# design.net
KiCad netlist of a schematic drawn in Altium Designer
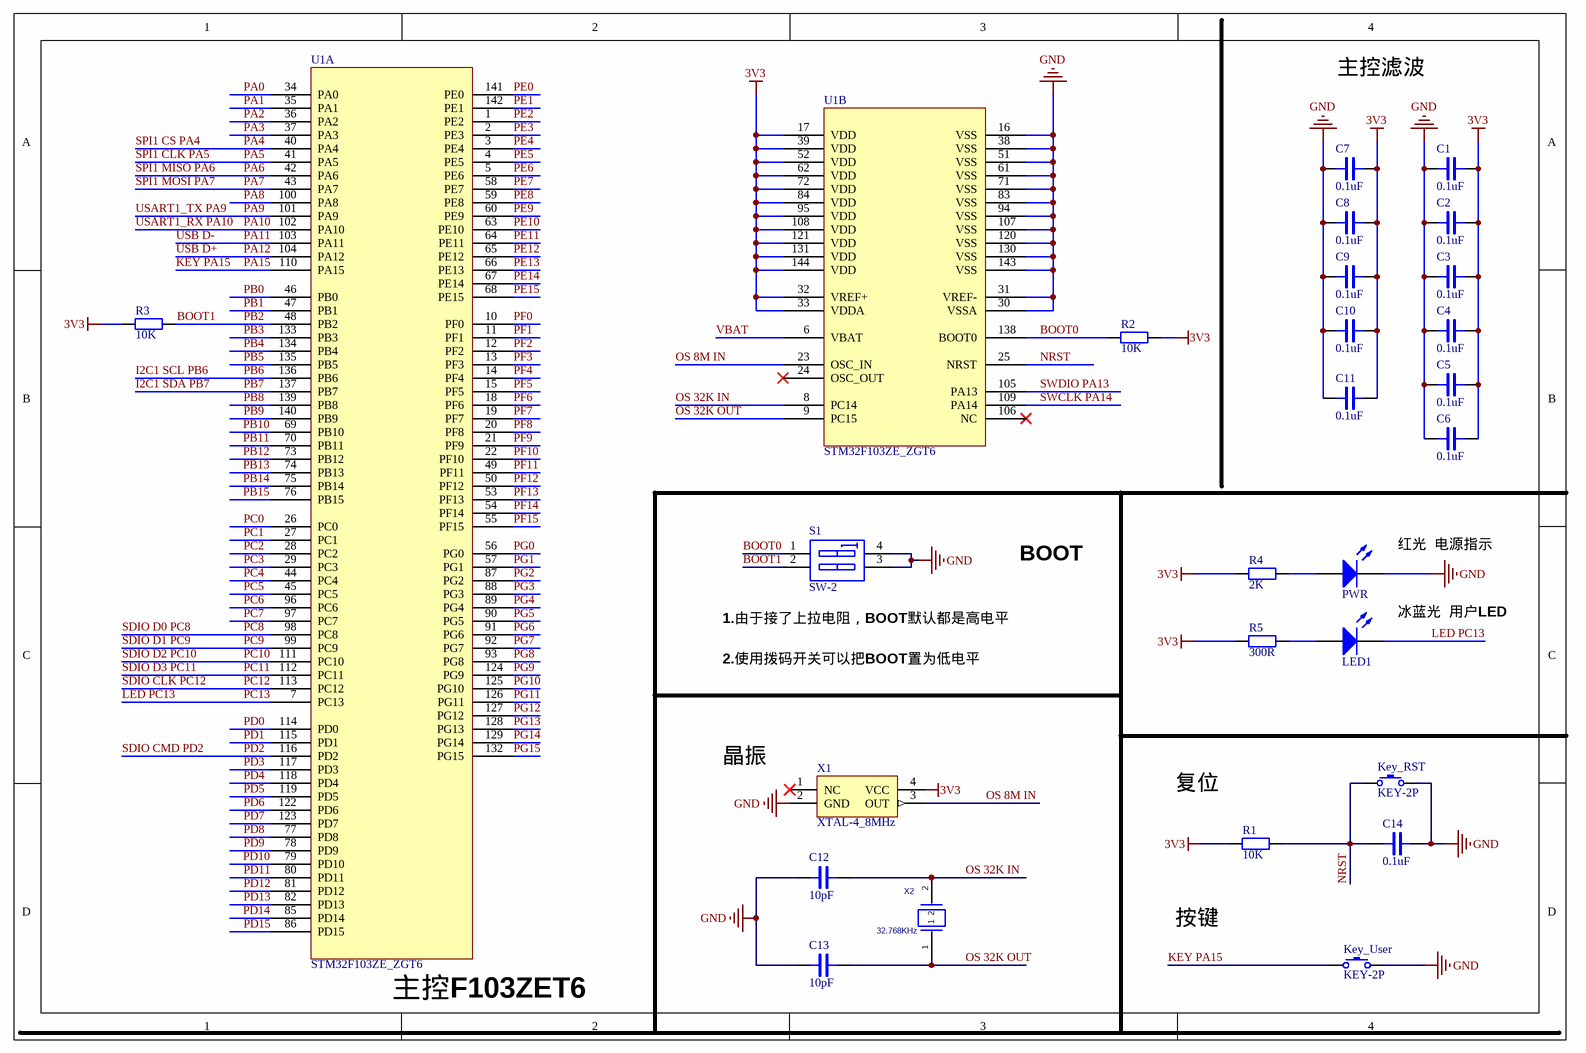
[diagram p0: 主控系统板.SchDoc]

(export (version "E")
  (design (tool "Eeschema 10.0.6"))
  (components
    (comp (ref "C1")
      (value "0.1uF")
      (footprint "0603")
      (description "Capacitor")
      (libsource (lib "General") (part "CAP"))
    )
    (comp (ref "C2")
      (value "0.1uF")
      (footprint "0603")
      (description "Capacitor")
      (libsource (lib "General") (part "CAP"))
    )
    (comp (ref "C3")
      (value "0.1uF")
      (footprint "0603")
      (description "Capacitor")
      (libsource (lib "General") (part "CAP"))
    )
    (comp (ref "C4")
      (value "0.1uF")
      (footprint "0603")
      (description "Capacitor")
      (libsource (lib "General") (part "CAP"))
    )
    (comp (ref "C5")
      (value "0.1uF")
      (footprint "0603")
      (description "Capacitor")
      (libsource (lib "General") (part "CAP"))
    )
    (comp (ref "C6")
      (value "0.1uF")
      (footprint "0603")
      (description "Capacitor")
      (libsource (lib "General") (part "CAP"))
    )
    (comp (ref "C7")
      (value "0.1uF")
      (footprint "0603")
      (description "Capacitor")
      (libsource (lib "General") (part "CAP"))
    )
    (comp (ref "C8")
      (value "0.1uF")
      (footprint "0603")
      (description "Capacitor")
      (libsource (lib "General") (part "CAP"))
    )
    (comp (ref "C9")
      (value "0.1uF")
      (footprint "0603")
      (description "Capacitor")
      (libsource (lib "General") (part "CAP"))
    )
    (comp (ref "C10")
      (value "0.1uF")
      (footprint "0603")
      (description "Capacitor")
      (libsource (lib "General") (part "CAP"))
    )
    (comp (ref "C11")
      (value "0.1uF")
      (footprint "0603")
      (description "Capacitor")
      (libsource (lib "General") (part "CAP"))
    )
    (comp (ref "C12")
      (value "10pF")
      (footprint "0603")
      (description "Capacitor")
      (libsource (lib "General") (part "CAP"))
    )
    (comp (ref "C13")
      (value "10pF")
      (footprint "0603")
      (description "Capacitor")
      (libsource (lib "General") (part "CAP"))
    )
    (comp (ref "C14")
      (value "0.1uF")
      (footprint "0603")
      (description "Capacitor")
      (libsource (lib "General") (part "CAP"))
    )
    (comp (ref "Key_RST")
      (value "KEY-2P")
      (footprint "TSW SMD-3*6*2.5")
      (description "Key")
      (libsource (lib "General") (part "KEY-2P"))
    )
    (comp (ref "Key_User")
      (value "KEY-2P")
      (footprint "TSW SMD-3*6*2.5")
      (description "Key")
      (libsource (lib "General") (part "KEY-2P"))
    )
    (comp (ref "LED1")
      (value "LED")
      (footprint "D0603")
      (libsource (lib "altium-import") (part "root_0_LED_"))
    )
    (comp (ref "PWR")
      (value "LED")
      (footprint "D0603")
      (libsource (lib "altium-import") (part "root_0_LED_"))
    )
    (comp (ref "R1")
      (value "10K")
      (footprint "0603")
      (description "Resistor")
      (libsource (lib "") (part "RES_1"))
    )
    (comp (ref "R2")
      (value "10K")
      (footprint "0603")
      (description "Resistor")
      (libsource (lib "") (part "RES_1"))
    )
    (comp (ref "R3")
      (value "10K")
      (footprint "0603")
      (description "Resistor")
      (libsource (lib "General") (part "RES"))
    )
    (comp (ref "R4")
      (value "2K")
      (footprint "0603")
      (description "Resistor")
      (libsource (lib "General") (part "RES"))
    )
    (comp (ref "R5")
      (value "300R")
      (footprint "0603")
      (description "Resistor")
      (libsource (lib "General") (part "RES"))
    )
    (comp (ref "S1")
      (value "SW-2")
      (footprint "CSW1.27 SMD-2P")
      (libsource (lib "altium-import") (part "root_0_SW-2_"))
    )
    (comp (ref "U1")
      (value "STM32F103ZE_ZGT6")
      (footprint "TQFP144_N")
      (libsource (lib "altium-import") (part "root_0_STM32F103ZE_ZGT6_"))
    )
    (comp (ref "X1")
      (value "XTAL-4_8MHz")
      (footprint "XTAL-5.0X3.2")
      (description "Oscillator")
      (libsource (lib "General") (part "XTAL-4"))
    )
    (comp (ref "X2")
      (value "32.768KHz")
      (footprint "3215")
      (description "CRYSTAL")
      (fields (field (name "Comment") "XTAL_32.768KHZ_3215"))
      (libsource (lib "altium-import") (part "root_0_XTAL_32.768KHZ_3215_"))
    )
  )
  (nets
    (net (code "1") (name "/BOOT0") (class "Default")
      (node (ref "R2") (pin "1") (pinfunction "1_1") (pintype "passive"))
      (node (ref "S1") (pin "1") (pinfunction "A1_1") (pintype "passive"))
      (node (ref "U1") (pin "138") (pinfunction "BOOT0_138") (pintype "passive"))
    )
    (net (code "2") (name "/BOOT1") (class "Default")
      (node (ref "R3") (pin "1") (pinfunction "1_1") (pintype "passive"))
      (node (ref "S1") (pin "2") (pinfunction "A2_2") (pintype "passive"))
      (node (ref "U1") (pin "48") (pinfunction "PB2_48") (pintype "passive"))
    )
    (net (code "3") (name "/I2C1 SCL PB6") (class "Default")
      (node (ref "U1") (pin "136") (pinfunction "PB6_136") (pintype "passive"))
    )
    (net (code "4") (name "/I2C1 SDA PB7") (class "Default")
      (node (ref "U1") (pin "137") (pinfunction "PB7_137") (pintype "passive"))
    )
    (net (code "5") (name "/KEY PA15") (class "Default")
      (node (ref "Key_User") (pin "1") (pinfunction "1_1") (pintype "passive"))
      (node (ref "U1") (pin "110") (pinfunction "PA15_110") (pintype "passive"))
    )
    (net (code "6") (name "/LED PC13") (class "Default")
      (node (ref "LED1") (pin "2") (pinfunction "K_2") (pintype "passive"))
      (node (ref "U1") (pin "7") (pinfunction "PC13_7") (pintype "passive"))
    )
    (net (code "7") (name "/NRST") (class "Default")
      (node (ref "C14") (pin "2") (pinfunction "2_2") (pintype "passive"))
      (node (ref "Key_RST") (pin "1") (pinfunction "1_1") (pintype "passive"))
      (node (ref "R1") (pin "2") (pinfunction "2_2") (pintype "passive"))
      (node (ref "U1") (pin "25") (pinfunction "NRST_25") (pintype "passive"))
    )
    (net (code "8") (name "/OS 8M IN") (class "Default")
      (node (ref "U1") (pin "23") (pinfunction "OSC_IN_23") (pintype "passive"))
      (node (ref "X1") (pin "3") (pinfunction "OUT_3") (pintype "output"))
    )
    (net (code "9") (name "/OS 32K IN") (class "Default")
      (node (ref "C12") (pin "1") (pinfunction "1_1") (pintype "passive"))
      (node (ref "U1") (pin "8") (pinfunction "PC14_8") (pintype "passive"))
      (node (ref "X2") (pin "2") (pinfunction "2_2") (pintype "passive"))
    )
    (net (code "10") (name "/OS 32K OUT") (class "Default")
      (node (ref "C13") (pin "1") (pinfunction "1_1") (pintype "passive"))
      (node (ref "U1") (pin "9") (pinfunction "PC15_9") (pintype "passive"))
      (node (ref "X2") (pin "1") (pinfunction "1_1") (pintype "passive"))
    )
    (net (code "11") (name "/PA0") (class "Default")
      (node (ref "U1") (pin "34") (pinfunction "PA0_34") (pintype "passive"))
    )
    (net (code "12") (name "/PA1") (class "Default")
      (node (ref "U1") (pin "35") (pinfunction "PA1_35") (pintype "passive"))
    )
    (net (code "13") (name "/PA2") (class "Default")
      (node (ref "U1") (pin "36") (pinfunction "PA2_36") (pintype "passive"))
    )
    (net (code "14") (name "/PA3") (class "Default")
      (node (ref "U1") (pin "37") (pinfunction "PA3_37") (pintype "passive"))
    )
    (net (code "15") (name "/PA4") (class "Default")
      (node (ref "U1") (pin "40") (pinfunction "PA4_40") (pintype "passive"))
    )
    (net (code "16") (name "/PA5") (class "Default")
      (node (ref "U1") (pin "41") (pinfunction "PA5_41") (pintype "passive"))
    )
    (net (code "17") (name "/PA6") (class "Default")
      (node (ref "U1") (pin "42") (pinfunction "PA6_42") (pintype "passive"))
    )
    (net (code "18") (name "/PA7") (class "Default")
      (node (ref "U1") (pin "43") (pinfunction "PA7_43") (pintype "passive"))
    )
    (net (code "19") (name "/PA8") (class "Default")
      (node (ref "U1") (pin "100") (pinfunction "PA8_100") (pintype "passive"))
    )
    (net (code "20") (name "/PA9") (class "Default")
      (node (ref "U1") (pin "101") (pinfunction "PA9_101") (pintype "passive"))
    )
    (net (code "21") (name "/PA10") (class "Default")
      (node (ref "U1") (pin "102") (pinfunction "PA10_102") (pintype "passive"))
    )
    (net (code "22") (name "/PA11") (class "Default")
      (node (ref "U1") (pin "103") (pinfunction "PA11_103") (pintype "passive"))
    )
    (net (code "23") (name "/PA12") (class "Default")
      (node (ref "U1") (pin "104") (pinfunction "PA12_104") (pintype "passive"))
    )
    (net (code "24") (name "/PB0") (class "Default")
      (node (ref "U1") (pin "46") (pinfunction "PB0_46") (pintype "passive"))
    )
    (net (code "25") (name "/PB1") (class "Default")
      (node (ref "U1") (pin "47") (pinfunction "PB1_47") (pintype "passive"))
    )
    (net (code "26") (name "/PB3") (class "Default")
      (node (ref "U1") (pin "133") (pinfunction "PB3_133") (pintype "passive"))
    )
    (net (code "27") (name "/PB4") (class "Default")
      (node (ref "U1") (pin "134") (pinfunction "PB4_134") (pintype "passive"))
    )
    (net (code "28") (name "/PB5") (class "Default")
      (node (ref "U1") (pin "135") (pinfunction "PB5_135") (pintype "passive"))
    )
    (net (code "29") (name "/PB8") (class "Default")
      (node (ref "U1") (pin "139") (pinfunction "PB8_139") (pintype "passive"))
    )
    (net (code "30") (name "/PB9") (class "Default")
      (node (ref "U1") (pin "140") (pinfunction "PB9_140") (pintype "passive"))
    )
    (net (code "31") (name "/PB10") (class "Default")
      (node (ref "U1") (pin "69") (pinfunction "PB10_69") (pintype "passive"))
    )
    (net (code "32") (name "/PB11") (class "Default")
      (node (ref "U1") (pin "70") (pinfunction "PB11_70") (pintype "passive"))
    )
    (net (code "33") (name "/PB12") (class "Default")
      (node (ref "U1") (pin "73") (pinfunction "PB12_73") (pintype "passive"))
    )
    (net (code "34") (name "/PB13") (class "Default")
      (node (ref "U1") (pin "74") (pinfunction "PB13_74") (pintype "passive"))
    )
    (net (code "35") (name "/PB14") (class "Default")
      (node (ref "U1") (pin "75") (pinfunction "PB14_75") (pintype "passive"))
    )
    (net (code "36") (name "/PB15") (class "Default")
      (node (ref "U1") (pin "76") (pinfunction "PB15_76") (pintype "passive"))
    )
    (net (code "37") (name "/PC0") (class "Default")
      (node (ref "U1") (pin "26") (pinfunction "PC0_26") (pintype "passive"))
    )
    (net (code "38") (name "/PC1") (class "Default")
      (node (ref "U1") (pin "27") (pinfunction "PC1_27") (pintype "passive"))
    )
    (net (code "39") (name "/PC2") (class "Default")
      (node (ref "U1") (pin "28") (pinfunction "PC2_28") (pintype "passive"))
    )
    (net (code "40") (name "/PC3") (class "Default")
      (node (ref "U1") (pin "29") (pinfunction "PC3_29") (pintype "passive"))
    )
    (net (code "41") (name "/PC4") (class "Default")
      (node (ref "U1") (pin "44") (pinfunction "PC4_44") (pintype "passive"))
    )
    (net (code "42") (name "/PC5") (class "Default")
      (node (ref "U1") (pin "45") (pinfunction "PC5_45") (pintype "passive"))
    )
    (net (code "43") (name "/PC6") (class "Default")
      (node (ref "U1") (pin "96") (pinfunction "PC6_96") (pintype "passive"))
    )
    (net (code "44") (name "/PC7") (class "Default")
      (node (ref "U1") (pin "97") (pinfunction "PC7_97") (pintype "passive"))
    )
    (net (code "45") (name "/PC8") (class "Default")
      (node (ref "U1") (pin "98") (pinfunction "PC8_98") (pintype "passive"))
    )
    (net (code "46") (name "/PC9") (class "Default")
      (node (ref "U1") (pin "99") (pinfunction "PC9_99") (pintype "passive"))
    )
    (net (code "47") (name "/PC10") (class "Default")
      (node (ref "U1") (pin "111") (pinfunction "PC10_111") (pintype "passive"))
    )
    (net (code "48") (name "/PC11") (class "Default")
      (node (ref "U1") (pin "112") (pinfunction "PC11_112") (pintype "passive"))
    )
    (net (code "49") (name "/PC12") (class "Default")
      (node (ref "U1") (pin "113") (pinfunction "PC12_113") (pintype "passive"))
    )
    (net (code "50") (name "/PD0") (class "Default")
      (node (ref "U1") (pin "114") (pinfunction "PD0_114") (pintype "passive"))
    )
    (net (code "51") (name "/PD1") (class "Default")
      (node (ref "U1") (pin "115") (pinfunction "PD1_115") (pintype "passive"))
    )
    (net (code "52") (name "/PD2") (class "Default")
      (node (ref "U1") (pin "116") (pinfunction "PD2_116") (pintype "passive"))
    )
    (net (code "53") (name "/PD3") (class "Default")
      (node (ref "U1") (pin "117") (pinfunction "PD3_117") (pintype "passive"))
    )
    (net (code "54") (name "/PD4") (class "Default")
      (node (ref "U1") (pin "118") (pinfunction "PD4_118") (pintype "passive"))
    )
    (net (code "55") (name "/PD5") (class "Default")
      (node (ref "U1") (pin "119") (pinfunction "PD5_119") (pintype "passive"))
    )
    (net (code "56") (name "/PD6") (class "Default")
      (node (ref "U1") (pin "122") (pinfunction "PD6_122") (pintype "passive"))
    )
    (net (code "57") (name "/PD7") (class "Default")
      (node (ref "U1") (pin "123") (pinfunction "PD7_123") (pintype "passive"))
    )
    (net (code "58") (name "/PD8") (class "Default")
      (node (ref "U1") (pin "77") (pinfunction "PD8_77") (pintype "passive"))
    )
    (net (code "59") (name "/PD9") (class "Default")
      (node (ref "U1") (pin "78") (pinfunction "PD9_78") (pintype "passive"))
    )
    (net (code "60") (name "/PD10") (class "Default")
      (node (ref "U1") (pin "79") (pinfunction "PD10_79") (pintype "passive"))
    )
    (net (code "61") (name "/PD11") (class "Default")
      (node (ref "U1") (pin "80") (pinfunction "PD11_80") (pintype "passive"))
    )
    (net (code "62") (name "/PD12") (class "Default")
      (node (ref "U1") (pin "81") (pinfunction "PD12_81") (pintype "passive"))
    )
    (net (code "63") (name "/PD13") (class "Default")
      (node (ref "U1") (pin "82") (pinfunction "PD13_82") (pintype "passive"))
    )
    (net (code "64") (name "/PD14") (class "Default")
      (node (ref "U1") (pin "85") (pinfunction "PD14_85") (pintype "passive"))
    )
    (net (code "65") (name "/PD15") (class "Default")
      (node (ref "U1") (pin "86") (pinfunction "PD15_86") (pintype "passive"))
    )
    (net (code "66") (name "/PE0") (class "Default")
      (node (ref "U1") (pin "141") (pinfunction "PE0_141") (pintype "passive"))
    )
    (net (code "67") (name "/PE1") (class "Default")
      (node (ref "U1") (pin "142") (pinfunction "PE1_142") (pintype "passive"))
    )
    (net (code "68") (name "/PE2") (class "Default")
      (node (ref "U1") (pin "1") (pinfunction "PE2_1") (pintype "passive"))
    )
    (net (code "69") (name "/PE3") (class "Default")
      (node (ref "U1") (pin "2") (pinfunction "PE3_2") (pintype "passive"))
    )
    (net (code "70") (name "/PE4") (class "Default")
      (node (ref "U1") (pin "3") (pinfunction "PE4_3") (pintype "passive"))
    )
    (net (code "71") (name "/PE5") (class "Default")
      (node (ref "U1") (pin "4") (pinfunction "PE5_4") (pintype "passive"))
    )
    (net (code "72") (name "/PE6") (class "Default")
      (node (ref "U1") (pin "5") (pinfunction "PE6_5") (pintype "passive"))
    )
    (net (code "73") (name "/PE7") (class "Default")
      (node (ref "U1") (pin "58") (pinfunction "PE7_58") (pintype "passive"))
    )
    (net (code "74") (name "/PE8") (class "Default")
      (node (ref "U1") (pin "59") (pinfunction "PE8_59") (pintype "passive"))
    )
    (net (code "75") (name "/PE9") (class "Default")
      (node (ref "U1") (pin "60") (pinfunction "PE9_60") (pintype "passive"))
    )
    (net (code "76") (name "/PE10") (class "Default")
      (node (ref "U1") (pin "63") (pinfunction "PE10_63") (pintype "passive"))
    )
    (net (code "77") (name "/PE11") (class "Default")
      (node (ref "U1") (pin "64") (pinfunction "PE11_64") (pintype "passive"))
    )
    (net (code "78") (name "/PE12") (class "Default")
      (node (ref "U1") (pin "65") (pinfunction "PE12_65") (pintype "passive"))
    )
    (net (code "79") (name "/PE13") (class "Default")
      (node (ref "U1") (pin "66") (pinfunction "PE13_66") (pintype "passive"))
    )
    (net (code "80") (name "/PE14") (class "Default")
      (node (ref "U1") (pin "67") (pinfunction "PE14_67") (pintype "passive"))
    )
    (net (code "81") (name "/PE15") (class "Default")
      (node (ref "U1") (pin "68") (pinfunction "PE15_68") (pintype "passive"))
    )
    (net (code "82") (name "/PF0") (class "Default")
      (node (ref "U1") (pin "10") (pinfunction "PF0_10") (pintype "passive"))
    )
    (net (code "83") (name "/PF1") (class "Default")
      (node (ref "U1") (pin "11") (pinfunction "PF1_11") (pintype "passive"))
    )
    (net (code "84") (name "/PF2") (class "Default")
      (node (ref "U1") (pin "12") (pinfunction "PF2_12") (pintype "passive"))
    )
    (net (code "85") (name "/PF3") (class "Default")
      (node (ref "U1") (pin "13") (pinfunction "PF3_13") (pintype "passive"))
    )
    (net (code "86") (name "/PF4") (class "Default")
      (node (ref "U1") (pin "14") (pinfunction "PF4_14") (pintype "passive"))
    )
    (net (code "87") (name "/PF5") (class "Default")
      (node (ref "U1") (pin "15") (pinfunction "PF5_15") (pintype "passive"))
    )
    (net (code "88") (name "/PF6") (class "Default")
      (node (ref "U1") (pin "18") (pinfunction "PF6_18") (pintype "passive"))
    )
    (net (code "89") (name "/PF7") (class "Default")
      (node (ref "U1") (pin "19") (pinfunction "PF7_19") (pintype "passive"))
    )
    (net (code "90") (name "/PF8") (class "Default")
      (node (ref "U1") (pin "20") (pinfunction "PF8_20") (pintype "passive"))
    )
    (net (code "91") (name "/PF9") (class "Default")
      (node (ref "U1") (pin "21") (pinfunction "PF9_21") (pintype "passive"))
    )
    (net (code "92") (name "/PF10") (class "Default")
      (node (ref "U1") (pin "22") (pinfunction "PF10_22") (pintype "passive"))
    )
    (net (code "93") (name "/PF11") (class "Default")
      (node (ref "U1") (pin "49") (pinfunction "PF11_49") (pintype "passive"))
    )
    (net (code "94") (name "/PF12") (class "Default")
      (node (ref "U1") (pin "50") (pinfunction "PF12_50") (pintype "passive"))
    )
    (net (code "95") (name "/PF13") (class "Default")
      (node (ref "U1") (pin "53") (pinfunction "PF13_53") (pintype "passive"))
    )
    (net (code "96") (name "/PF14") (class "Default")
      (node (ref "U1") (pin "54") (pinfunction "PF14_54") (pintype "passive"))
    )
    (net (code "97") (name "/PF15") (class "Default")
      (node (ref "U1") (pin "55") (pinfunction "PF15_55") (pintype "passive"))
    )
    (net (code "98") (name "/PG0") (class "Default")
      (node (ref "U1") (pin "56") (pinfunction "PG0_56") (pintype "passive"))
    )
    (net (code "99") (name "/PG1") (class "Default")
      (node (ref "U1") (pin "57") (pinfunction "PG1_57") (pintype "passive"))
    )
    (net (code "100") (name "/PG2") (class "Default")
      (node (ref "U1") (pin "87") (pinfunction "PG2_87") (pintype "passive"))
    )
    (net (code "101") (name "/PG3") (class "Default")
      (node (ref "U1") (pin "88") (pinfunction "PG3_88") (pintype "passive"))
    )
    (net (code "102") (name "/PG4") (class "Default")
      (node (ref "U1") (pin "89") (pinfunction "PG4_89") (pintype "passive"))
    )
    (net (code "103") (name "/PG5") (class "Default")
      (node (ref "U1") (pin "90") (pinfunction "PG5_90") (pintype "passive"))
    )
    (net (code "104") (name "/PG6") (class "Default")
      (node (ref "U1") (pin "91") (pinfunction "PG6_91") (pintype "passive"))
    )
    (net (code "105") (name "/PG7") (class "Default")
      (node (ref "U1") (pin "92") (pinfunction "PG7_92") (pintype "passive"))
    )
    (net (code "106") (name "/PG8") (class "Default")
      (node (ref "U1") (pin "93") (pinfunction "PG8_93") (pintype "passive"))
    )
    (net (code "107") (name "/PG9") (class "Default")
      (node (ref "U1") (pin "124") (pinfunction "PG9_124") (pintype "passive"))
    )
    (net (code "108") (name "/PG10") (class "Default")
      (node (ref "U1") (pin "125") (pinfunction "PG10_125") (pintype "passive"))
    )
    (net (code "109") (name "/PG11") (class "Default")
      (node (ref "U1") (pin "126") (pinfunction "PG11_126") (pintype "passive"))
    )
    (net (code "110") (name "/PG12") (class "Default")
      (node (ref "U1") (pin "127") (pinfunction "PG12_127") (pintype "passive"))
    )
    (net (code "111") (name "/PG13") (class "Default")
      (node (ref "U1") (pin "128") (pinfunction "PG13_128") (pintype "passive"))
    )
    (net (code "112") (name "/PG14") (class "Default")
      (node (ref "U1") (pin "129") (pinfunction "PG14_129") (pintype "passive"))
    )
    (net (code "113") (name "/PG15") (class "Default")
      (node (ref "U1") (pin "132") (pinfunction "PG15_132") (pintype "passive"))
    )
    (net (code "114") (name "/SWCLK PA14") (class "Default")
      (node (ref "U1") (pin "109") (pinfunction "PA14_109") (pintype "passive"))
    )
    (net (code "115") (name "/SWDIO PA13") (class "Default")
      (node (ref "U1") (pin "105") (pinfunction "PA13_105") (pintype "passive"))
    )
    (net (code "116") (name "/VBAT") (class "Default")
      (node (ref "U1") (pin "6") (pinfunction "VBAT_6") (pintype "passive"))
    )
    (net (code "117") (name "3V3") (class "Default")
      (node (ref "C1") (pin "2") (pinfunction "2_2") (pintype "passive"))
      (node (ref "C10") (pin "2") (pinfunction "2_2") (pintype "passive"))
      (node (ref "C11") (pin "2") (pinfunction "2_2") (pintype "passive"))
      (node (ref "C2") (pin "2") (pinfunction "2_2") (pintype "passive"))
      (node (ref "C3") (pin "2") (pinfunction "2_2") (pintype "passive"))
      (node (ref "C4") (pin "2") (pinfunction "2_2") (pintype "passive"))
      (node (ref "C5") (pin "2") (pinfunction "2_2") (pintype "passive"))
      (node (ref "C6") (pin "2") (pinfunction "2_2") (pintype "passive"))
      (node (ref "C7") (pin "2") (pinfunction "2_2") (pintype "passive"))
      (node (ref "C8") (pin "2") (pinfunction "2_2") (pintype "passive"))
      (node (ref "C9") (pin "2") (pinfunction "2_2") (pintype "passive"))
      (node (ref "R1") (pin "1") (pinfunction "1_1") (pintype "passive"))
      (node (ref "R2") (pin "2") (pinfunction "2_2") (pintype "passive"))
      (node (ref "R3") (pin "2") (pinfunction "2_2") (pintype "passive"))
      (node (ref "R4") (pin "2") (pinfunction "2_2") (pintype "passive"))
      (node (ref "R5") (pin "2") (pinfunction "2_2") (pintype "passive"))
      (node (ref "U1") (pin "108") (pinfunction "VDD_108") (pintype "passive"))
      (node (ref "U1") (pin "121") (pinfunction "VDD_121") (pintype "passive"))
      (node (ref "U1") (pin "131") (pinfunction "VDD_131") (pintype "passive"))
      (node (ref "U1") (pin "144") (pinfunction "VDD_144") (pintype "passive"))
      (node (ref "U1") (pin "17") (pinfunction "VDD_17") (pintype "passive"))
      (node (ref "U1") (pin "32") (pinfunction "VREF+_32") (pintype "passive"))
      (node (ref "U1") (pin "33") (pinfunction "VDDA_33") (pintype "passive"))
      (node (ref "U1") (pin "39") (pinfunction "VDD_39") (pintype "passive"))
      (node (ref "U1") (pin "52") (pinfunction "VDD_52") (pintype "passive"))
      (node (ref "U1") (pin "62") (pinfunction "VDD_62") (pintype "passive"))
      (node (ref "U1") (pin "72") (pinfunction "VDD_72") (pintype "passive"))
      (node (ref "U1") (pin "84") (pinfunction "VDD_84") (pintype "passive"))
      (node (ref "U1") (pin "95") (pinfunction "VDD_95") (pintype "passive"))
      (node (ref "X1") (pin "4") (pinfunction "VCC_4") (pintype "power_in"))
    )
    (net (code "118") (name "GND") (class "Default")
      (node (ref "C1") (pin "1") (pinfunction "1_1") (pintype "passive"))
      (node (ref "C10") (pin "1") (pinfunction "1_1") (pintype "passive"))
      (node (ref "C11") (pin "1") (pinfunction "1_1") (pintype "passive"))
      (node (ref "C12") (pin "2") (pinfunction "2_2") (pintype "passive"))
      (node (ref "C13") (pin "2") (pinfunction "2_2") (pintype "passive"))
      (node (ref "C14") (pin "1") (pinfunction "1_1") (pintype "passive"))
      (node (ref "C2") (pin "1") (pinfunction "1_1") (pintype "passive"))
      (node (ref "C3") (pin "1") (pinfunction "1_1") (pintype "passive"))
      (node (ref "C4") (pin "1") (pinfunction "1_1") (pintype "passive"))
      (node (ref "C5") (pin "1") (pinfunction "1_1") (pintype "passive"))
      (node (ref "C6") (pin "1") (pinfunction "1_1") (pintype "passive"))
      (node (ref "C7") (pin "1") (pinfunction "1_1") (pintype "passive"))
      (node (ref "C8") (pin "1") (pinfunction "1_1") (pintype "passive"))
      (node (ref "C9") (pin "1") (pinfunction "1_1") (pintype "passive"))
      (node (ref "Key_RST") (pin "2") (pinfunction "2_2") (pintype "passive"))
      (node (ref "Key_User") (pin "2") (pinfunction "2_2") (pintype "passive"))
      (node (ref "PWR") (pin "2") (pinfunction "K_2") (pintype "passive"))
      (node (ref "S1") (pin "3") (pinfunction "B2_3") (pintype "passive"))
      (node (ref "S1") (pin "4") (pinfunction "B1_4") (pintype "passive"))
      (node (ref "U1") (pin "107") (pinfunction "VSS_107") (pintype "passive"))
      (node (ref "U1") (pin "120") (pinfunction "VSS_120") (pintype "passive"))
      (node (ref "U1") (pin "130") (pinfunction "VSS_130") (pintype "passive"))
      (node (ref "U1") (pin "143") (pinfunction "VSS_143") (pintype "passive"))
      (node (ref "U1") (pin "16") (pinfunction "VSS_16") (pintype "passive"))
      (node (ref "U1") (pin "30") (pinfunction "VSSA_30") (pintype "passive"))
      (node (ref "U1") (pin "31") (pinfunction "VREF-_31") (pintype "passive"))
      (node (ref "U1") (pin "38") (pinfunction "VSS_38") (pintype "passive"))
      (node (ref "U1") (pin "51") (pinfunction "VSS_51") (pintype "passive"))
      (node (ref "U1") (pin "61") (pinfunction "VSS_61") (pintype "passive"))
      (node (ref "U1") (pin "71") (pinfunction "VSS_71") (pintype "passive"))
      (node (ref "U1") (pin "83") (pinfunction "VSS_83") (pintype "passive"))
      (node (ref "U1") (pin "94") (pinfunction "VSS_94") (pintype "passive"))
      (node (ref "X1") (pin "2") (pinfunction "GND_2") (pintype "power_in"))
    )
    (net (code "119") (name "Net-(LED1-A)") (class "Default")
      (node (ref "LED1") (pin "1") (pinfunction "A_1") (pintype "passive"))
      (node (ref "R5") (pin "1") (pinfunction "1_1") (pintype "passive"))
    )
    (net (code "120") (name "Net-(PWR-A)") (class "Default")
      (node (ref "PWR") (pin "1") (pinfunction "A_1") (pintype "passive"))
      (node (ref "R4") (pin "1") (pinfunction "1_1") (pintype "passive"))
    )
    (net (code "121") (name "unconnected-(U1B-NC-Pad106)") (class "Default")
      (node (ref "U1") (pin "106") (pinfunction "NC_106") (pintype "passive+no_connect"))
    )
    (net (code "122") (name "unconnected-(U1B-OSC_OUT-Pad24)") (class "Default")
      (node (ref "U1") (pin "24") (pinfunction "OSC_OUT_24") (pintype "passive+no_connect"))
    )
    (net (code "123") (name "unconnected-(X1-NC-Pad1)") (class "Default")
      (node (ref "X1") (pin "1") (pinfunction "NC_1") (pintype "passive+no_connect"))
    )
  )
)
